# Tapuino_1_2.net
KiCad netlist of a schematic drawn in EAGLE
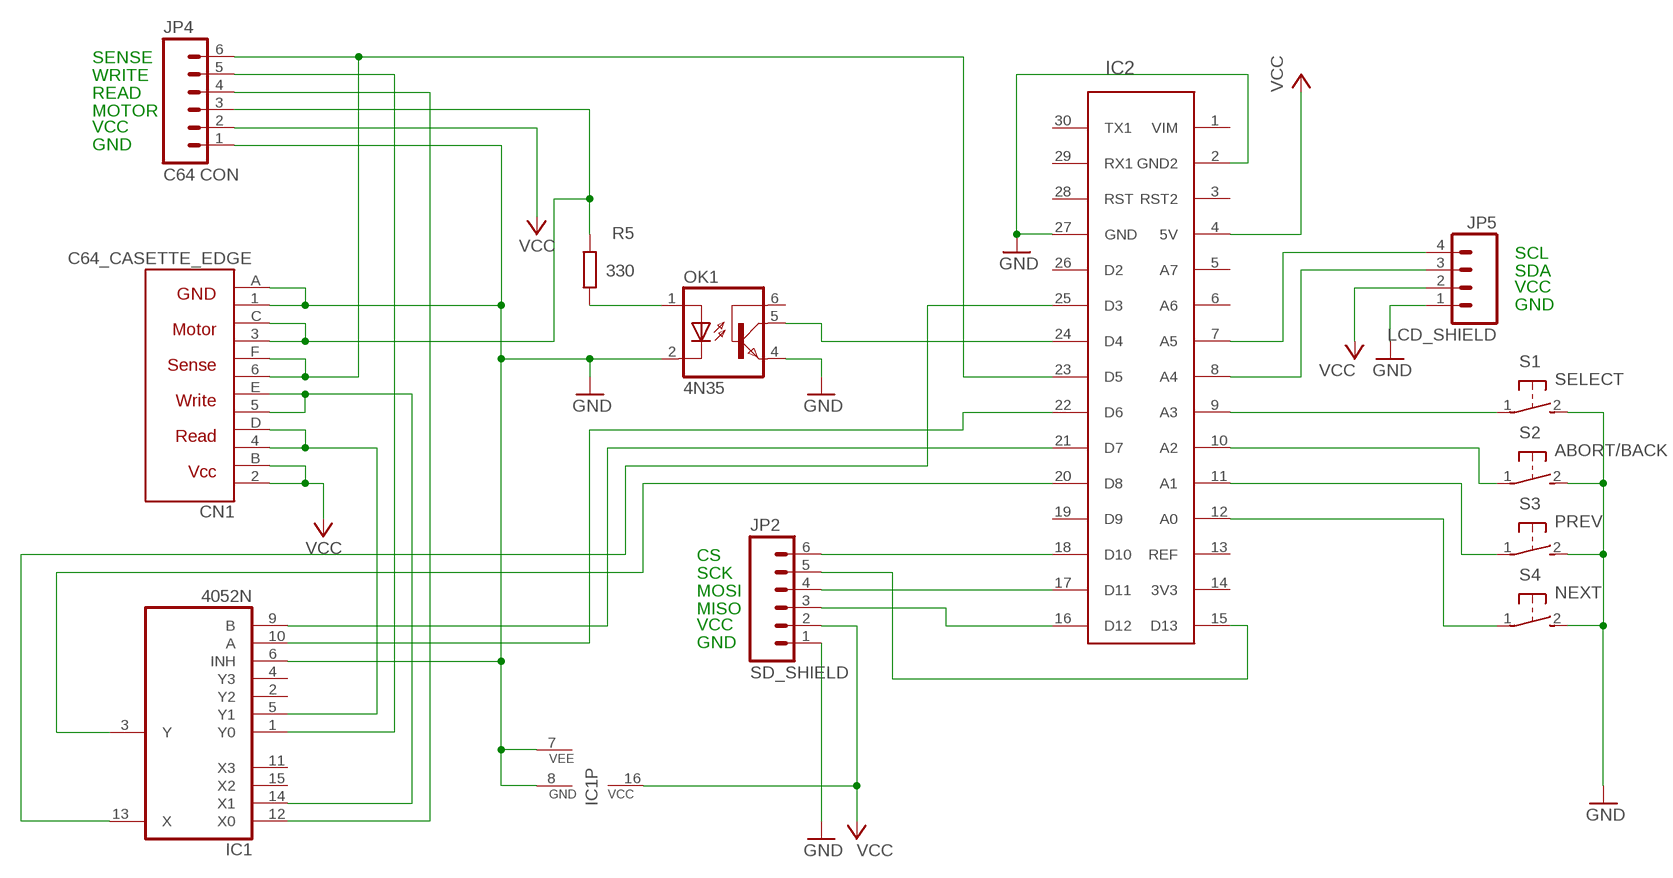
[diagram p0: schematic, sheet 1]

(export (version "E")
  (design (tool "Eeschema 10.0.6"))
  (components
    (comp (ref "CN1")
      (value "C64_CASETTE_EDGE")
      (footprint "eagle-import:C64_CASSETTE")
      (libsource (lib "eagle-import") (part "C64_CASETTE_EDGE"))
    )
    (comp (ref "IC1")
      (value "4052N")
      (footprint "eagle-import:DIL16")
      (libsource (lib "eagle-import") (part "4052N"))
    )
    (comp (ref "IC2")
      (value "ARDUINO_NANO_V3")
      (footprint "eagle-import:NANO_V3")
      (libsource (lib "eagle-import") (part "ARDUINO_NANO_V3"))
    )
    (comp (ref "JP2")
      (value "SD_SHIELD")
      (footprint "eagle-import:1X06_LOCK_LONGPADS")
      (libsource (lib "eagle-import") (part "M06LOCK_LONGPADS"))
    )
    (comp (ref "JP4")
      (value "C64 CON")
      (footprint "eagle-import:1X06_LOCK_LONGPADS")
      (libsource (lib "eagle-import") (part "M06LOCK_LONGPADS"))
    )
    (comp (ref "JP5")
      (value "LCD_SHIELD")
      (footprint "eagle-import:1X04_LOCK_LONGPADS")
      (libsource (lib "eagle-import") (part "M04LOCK_LONGPADS"))
    )
    (comp (ref "OK1")
      (value "4N35")
      (footprint "eagle-import:DIL06")
      (fields (field (name "MF") "FAIRCHILD SEMICONDUCTOR"))
      (libsource (lib "eagle-import") (part "4N35"))
    )
    (comp (ref "R5")
      (value "330")
      (footprint "eagle-import:0207_10")
      (libsource (lib "eagle-import") (part "R-EU_0207/10"))
    )
    (comp (ref "S1")
      (value "SELECT")
      (footprint "eagle-import:B3F-31XX")
      (fields (field (name "MPN") "B3F-3100"))
      (libsource (lib "eagle-import") (part "31-XX"))
    )
    (comp (ref "S2")
      (value "ABORT/BACK")
      (footprint "eagle-import:B3F-31XX")
      (fields (field (name "MPN") "B3F-3100"))
      (libsource (lib "eagle-import") (part "31-XX"))
    )
    (comp (ref "S3")
      (value "PREV")
      (footprint "eagle-import:B3F-31XX")
      (fields (field (name "MPN") "B3F-3100"))
      (libsource (lib "eagle-import") (part "31-XX"))
    )
    (comp (ref "S4")
      (value "NEXT")
      (footprint "eagle-import:B3F-31XX")
      (fields (field (name "MPN") "B3F-3100"))
      (libsource (lib "eagle-import") (part "31-XX"))
    )
  )
  (nets
    (net (code "1") (name "GND") (class "Default")
      (node (ref "CN1") (pin "1") (pinfunction "GND1_1") (pintype "passive"))
      (node (ref "CN1") (pin "A") (pinfunction "GND2_A") (pintype "passive"))
      (node (ref "IC1") (pin "6") (pinfunction "INH_6") (pintype "input"))
      (node (ref "IC1") (pin "7") (pinfunction "VEE_7") (pintype "power_in"))
      (node (ref "IC1") (pin "8") (pinfunction "GND_8") (pintype "power_in"))
      (node (ref "IC2") (pin "2") (pinfunction "GND2_2") (pintype "bidirectional"))
      (node (ref "IC2") (pin "27") (pinfunction "GND_27") (pintype "bidirectional"))
      (node (ref "JP2") (pin "1") (pinfunction "1_1") (pintype "passive"))
      (node (ref "JP4") (pin "1") (pinfunction "1_1") (pintype "passive"))
      (node (ref "JP5") (pin "1") (pinfunction "1_1") (pintype "passive"))
      (node (ref "OK1") (pin "2") (pinfunction "C_2") (pintype "passive"))
      (node (ref "OK1") (pin "4") (pinfunction "EMI_4") (pintype "passive"))
      (node (ref "S1") (pin "2") (pinfunction "S_2") (pintype "passive"))
      (node (ref "S2") (pin "2") (pinfunction "S_2") (pintype "passive"))
      (node (ref "S3") (pin "2") (pinfunction "S_2") (pintype "passive"))
      (node (ref "S4") (pin "2") (pinfunction "S_2") (pintype "passive"))
    )
    (net (code "2") (name "Net-(CN1-MOTOR1)") (class "Default")
      (node (ref "CN1") (pin "3") (pinfunction "MOTOR1_3") (pintype "input"))
      (node (ref "CN1") (pin "C") (pinfunction "MOTOR2_C") (pintype "input"))
      (node (ref "JP4") (pin "3") (pinfunction "3_3") (pintype "passive"))
      (node (ref "R5") (pin "2") (pinfunction "2_2") (pintype "passive"))
    )
    (net (code "3") (name "Net-(CN1-READ1)") (class "Default")
      (node (ref "CN1") (pin "4") (pinfunction "READ1_4") (pintype "output"))
      (node (ref "CN1") (pin "D") (pinfunction "READ2_D") (pintype "passive"))
      (node (ref "IC1") (pin "5") (pinfunction "Y1_5") (pintype "bidirectional"))
    )
    (net (code "4") (name "Net-(CN1-SENSE1)") (class "Default")
      (node (ref "CN1") (pin "6") (pinfunction "SENSE1_6") (pintype "output"))
      (node (ref "CN1") (pin "F") (pinfunction "SENSE2_F") (pintype "passive"))
      (node (ref "IC2") (pin "23") (pinfunction "D5_23") (pintype "bidirectional"))
      (node (ref "JP4") (pin "6") (pinfunction "6_6") (pintype "passive"))
    )
    (net (code "5") (name "Net-(CN1-WRITE1)") (class "Default")
      (node (ref "CN1") (pin "5") (pinfunction "WRITE1_5") (pintype "input"))
      (node (ref "CN1") (pin "E") (pinfunction "WRITE2_E") (pintype "input"))
      (node (ref "IC1") (pin "14") (pinfunction "X1_14") (pintype "bidirectional"))
    )
    (net (code "6") (name "Net-(IC1A-A)") (class "Default")
      (node (ref "IC1") (pin "10") (pinfunction "A_10") (pintype "input"))
      (node (ref "IC2") (pin "22") (pinfunction "D6_22") (pintype "bidirectional"))
    )
    (net (code "7") (name "Net-(IC1A-B)") (class "Default")
      (node (ref "IC1") (pin "9") (pinfunction "B_9") (pintype "input"))
      (node (ref "IC2") (pin "21") (pinfunction "D7_21") (pintype "bidirectional"))
    )
    (net (code "8") (name "Net-(IC1A-X)") (class "Default")
      (node (ref "IC1") (pin "13") (pinfunction "X_13") (pintype "bidirectional"))
      (node (ref "IC2") (pin "25") (pinfunction "D3_25") (pintype "bidirectional"))
    )
    (net (code "9") (name "Net-(IC1A-X0)") (class "Default")
      (node (ref "IC1") (pin "12") (pinfunction "X0_12") (pintype "bidirectional"))
      (node (ref "JP4") (pin "4") (pinfunction "4_4") (pintype "passive"))
    )
    (net (code "10") (name "Net-(IC1A-Y)") (class "Default")
      (node (ref "IC1") (pin "3") (pinfunction "Y_3") (pintype "bidirectional"))
      (node (ref "IC2") (pin "20") (pinfunction "D8_20") (pintype "bidirectional"))
    )
    (net (code "11") (name "Net-(IC1A-Y0)") (class "Default")
      (node (ref "IC1") (pin "1") (pinfunction "Y0_1") (pintype "bidirectional"))
      (node (ref "JP4") (pin "5") (pinfunction "5_5") (pintype "passive"))
    )
    (net (code "12") (name "Net-(IC2-A0)") (class "Default")
      (node (ref "IC2") (pin "12") (pinfunction "A0_12") (pintype "bidirectional"))
      (node (ref "S4") (pin "1") (pinfunction "P_1") (pintype "passive"))
    )
    (net (code "13") (name "Net-(IC2-A1)") (class "Default")
      (node (ref "IC2") (pin "11") (pinfunction "A1_11") (pintype "bidirectional"))
      (node (ref "S3") (pin "1") (pinfunction "P_1") (pintype "passive"))
    )
    (net (code "14") (name "Net-(IC2-A2)") (class "Default")
      (node (ref "IC2") (pin "10") (pinfunction "A2_10") (pintype "bidirectional"))
      (node (ref "S2") (pin "1") (pinfunction "P_1") (pintype "passive"))
    )
    (net (code "15") (name "Net-(IC2-A3)") (class "Default")
      (node (ref "IC2") (pin "9") (pinfunction "A3_9") (pintype "bidirectional"))
      (node (ref "S1") (pin "1") (pinfunction "P_1") (pintype "passive"))
    )
    (net (code "16") (name "Net-(IC2-A4)") (class "Default")
      (node (ref "IC2") (pin "8") (pinfunction "A4_8") (pintype "bidirectional"))
      (node (ref "JP5") (pin "3") (pinfunction "3_3") (pintype "passive"))
    )
    (net (code "17") (name "Net-(IC2-A5)") (class "Default")
      (node (ref "IC2") (pin "7") (pinfunction "A5_7") (pintype "bidirectional"))
      (node (ref "JP5") (pin "4") (pinfunction "4_4") (pintype "passive"))
    )
    (net (code "18") (name "Net-(IC2-D4)") (class "Default")
      (node (ref "IC2") (pin "24") (pinfunction "D4_24") (pintype "bidirectional"))
      (node (ref "OK1") (pin "5") (pinfunction "COL_5") (pintype "passive"))
    )
    (net (code "19") (name "Net-(IC2-D10)") (class "Default")
      (node (ref "IC2") (pin "18") (pinfunction "D10_18") (pintype "bidirectional"))
      (node (ref "JP2") (pin "6") (pinfunction "6_6") (pintype "passive"))
    )
    (net (code "20") (name "Net-(IC2-D11)") (class "Default")
      (node (ref "IC2") (pin "17") (pinfunction "D11_17") (pintype "bidirectional"))
      (node (ref "JP2") (pin "4") (pinfunction "4_4") (pintype "passive"))
    )
    (net (code "21") (name "Net-(IC2-D12)") (class "Default")
      (node (ref "IC2") (pin "16") (pinfunction "D12_16") (pintype "bidirectional"))
      (node (ref "JP2") (pin "3") (pinfunction "3_3") (pintype "passive"))
    )
    (net (code "22") (name "Net-(IC2-D13)") (class "Default")
      (node (ref "IC2") (pin "15") (pinfunction "D13_15") (pintype "bidirectional"))
      (node (ref "JP2") (pin "5") (pinfunction "5_5") (pintype "passive"))
    )
    (net (code "23") (name "Net-(OK1-A)") (class "Default")
      (node (ref "OK1") (pin "1") (pinfunction "A_1") (pintype "passive"))
      (node (ref "R5") (pin "1") (pinfunction "1_1") (pintype "passive"))
    )
    (net (code "24") (name "VCC") (class "Default")
      (node (ref "CN1") (pin "2") (pinfunction "VCC1_2") (pintype "passive"))
      (node (ref "CN1") (pin "B") (pinfunction "VCC2_B") (pintype "passive"))
      (node (ref "IC1") (pin "16") (pinfunction "VCC_16") (pintype "power_in"))
      (node (ref "IC2") (pin "4") (pinfunction "5V_4") (pintype "bidirectional"))
      (node (ref "JP2") (pin "2") (pinfunction "2_2") (pintype "passive"))
      (node (ref "JP4") (pin "2") (pinfunction "2_2") (pintype "passive"))
      (node (ref "JP5") (pin "2") (pinfunction "2_2") (pintype "passive"))
    )
    (net (code "25") (name "unconnected-(IC1A-X2-Pad15)") (class "Default")
      (node (ref "IC1") (pin "15") (pinfunction "X2_15") (pintype "bidirectional"))
    )
    (net (code "26") (name "unconnected-(IC1A-X3-Pad11)") (class "Default")
      (node (ref "IC1") (pin "11") (pinfunction "X3_11") (pintype "bidirectional"))
    )
    (net (code "27") (name "unconnected-(IC1A-Y2-Pad2)") (class "Default")
      (node (ref "IC1") (pin "2") (pinfunction "Y2_2") (pintype "bidirectional"))
    )
    (net (code "28") (name "unconnected-(IC1A-Y3-Pad4)") (class "Default")
      (node (ref "IC1") (pin "4") (pinfunction "Y3_4") (pintype "bidirectional"))
    )
    (net (code "29") (name "unconnected-(IC2-3V3-Pad14)") (class "Default")
      (node (ref "IC2") (pin "14") (pinfunction "3V3_14") (pintype "bidirectional"))
    )
    (net (code "30") (name "unconnected-(IC2-A6-Pad6)") (class "Default")
      (node (ref "IC2") (pin "6") (pinfunction "A6_6") (pintype "bidirectional"))
    )
    (net (code "31") (name "unconnected-(IC2-A7-Pad5)") (class "Default")
      (node (ref "IC2") (pin "5") (pinfunction "A7_5") (pintype "bidirectional"))
    )
    (net (code "32") (name "unconnected-(IC2-D2-Pad26)") (class "Default")
      (node (ref "IC2") (pin "26") (pinfunction "D2_26") (pintype "bidirectional"))
    )
    (net (code "33") (name "unconnected-(IC2-D9-Pad19)") (class "Default")
      (node (ref "IC2") (pin "19") (pinfunction "D9_19") (pintype "bidirectional"))
    )
    (net (code "34") (name "unconnected-(IC2-REF-Pad13)") (class "Default")
      (node (ref "IC2") (pin "13") (pinfunction "REF_13") (pintype "bidirectional"))
    )
    (net (code "35") (name "unconnected-(IC2-RST-Pad28)") (class "Default")
      (node (ref "IC2") (pin "28") (pinfunction "RST_28") (pintype "bidirectional"))
    )
    (net (code "36") (name "unconnected-(IC2-RST2-Pad3)") (class "Default")
      (node (ref "IC2") (pin "3") (pinfunction "RST2_3") (pintype "bidirectional"))
    )
    (net (code "37") (name "unconnected-(IC2-RX1-Pad29)") (class "Default")
      (node (ref "IC2") (pin "29") (pinfunction "RX1_29") (pintype "bidirectional"))
    )
    (net (code "38") (name "unconnected-(IC2-TX1-Pad30)") (class "Default")
      (node (ref "IC2") (pin "30") (pinfunction "TX1_30") (pintype "bidirectional"))
    )
    (net (code "39") (name "unconnected-(IC2-VIM-Pad1)") (class "Default")
      (node (ref "IC2") (pin "1") (pinfunction "VIM_1") (pintype "bidirectional"))
    )
    (net (code "40") (name "unconnected-(OK1-BAS-Pad6)") (class "Default")
      (node (ref "OK1") (pin "6") (pinfunction "BAS_6") (pintype "passive"))
    )
  )
)
